# 08_AuxConnectors.net
KiCad netlist of a schematic drawn in Altium Designer
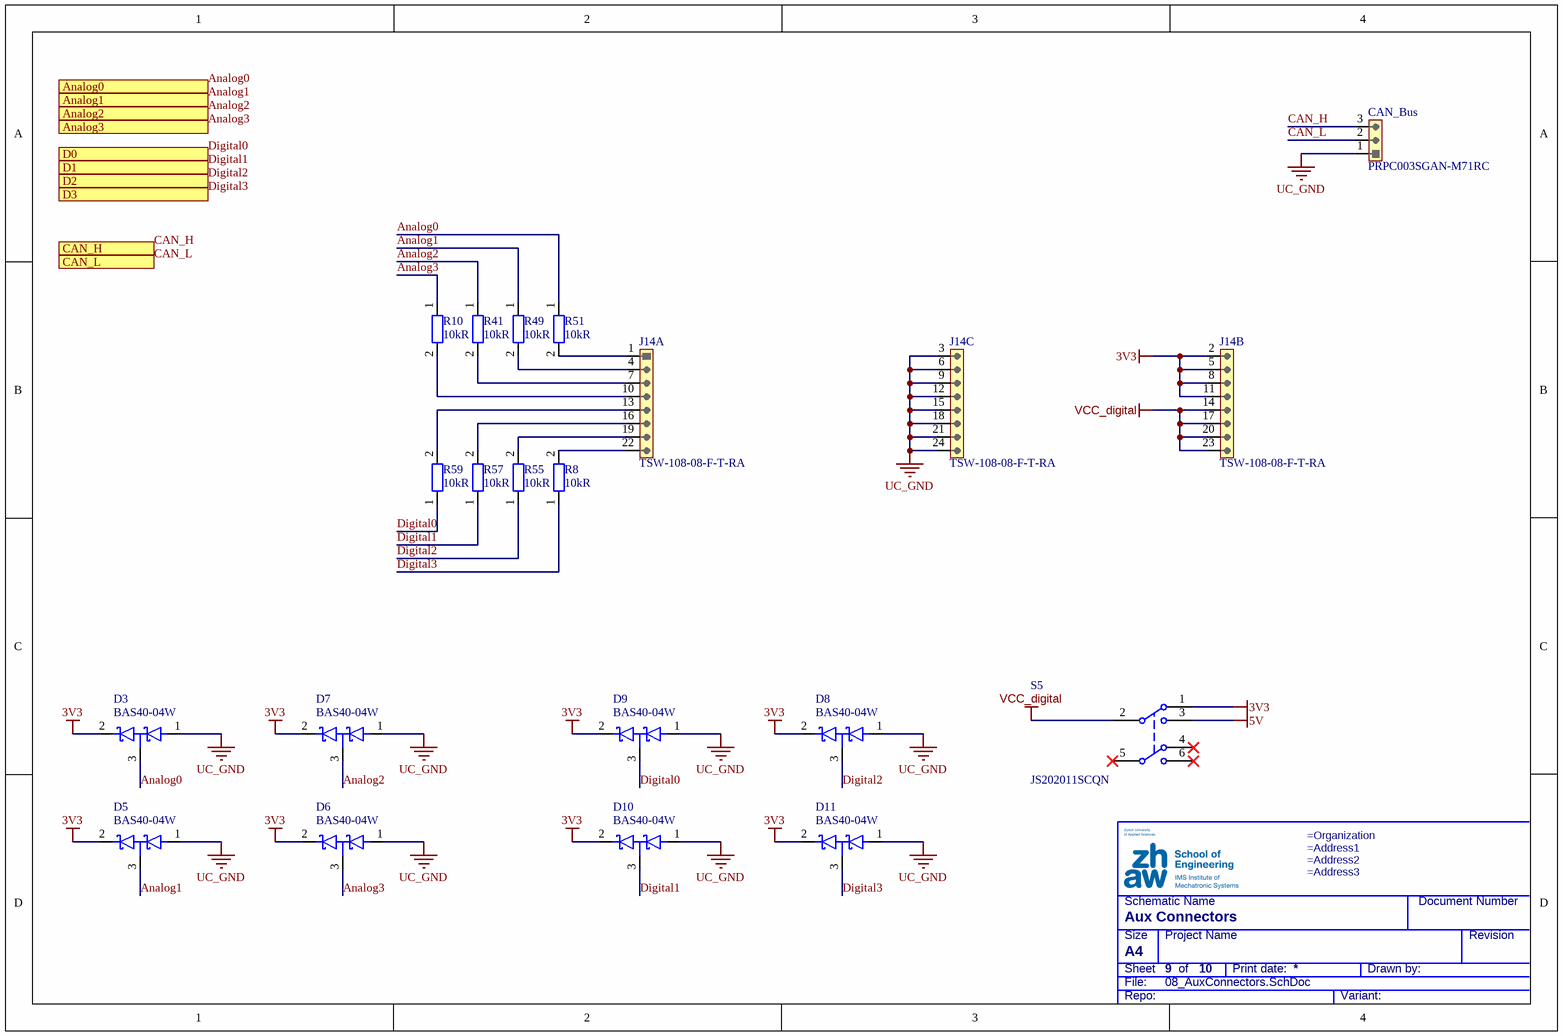
[diagram p0: 08_AuxConnectors.SchDoc]

(export (version "E")
  (design (tool "Eeschema 10.0.6"))
  (components
    (comp (ref "CAN_Bus")
      (value "PRPC003SGAN-M71RC")
      (footprint "HD254_1x3_MH")
      (description "Header, 1x3Pin, Pitch 2.54mm, Male, Horizontal, THT")
      (fields (field (name "MANUFACTURER") "Sullins Connector Solutions"))
      (libsource (lib "Altium Concord Pro on Altium 365") (part "Header 1x03 m"))
    )
    (comp (ref "D3")
      (value "BAS40-04W")
      (footprint "SOT65P220X110-3L")
      (description "Schottky Diode, 40V, 120mA, SOT323, 2 in series")
      (fields (field (name "VOLTAGE") "40V"))
      (libsource (lib "Altium Concord Pro on Altium 365") (part "D-SKY-AKC-3"))
    )
    (comp (ref "D5")
      (value "BAS40-04W")
      (footprint "SOT65P220X110-3L")
      (description "Schottky Diode, 40V, 120mA, SOT323, 2 in series")
      (fields (field (name "VOLTAGE") "40V"))
      (libsource (lib "Altium Concord Pro on Altium 365") (part "D-SKY-AKC-3"))
    )
    (comp (ref "D6")
      (value "BAS40-04W")
      (footprint "SOT65P220X110-3L")
      (description "Schottky Diode, 40V, 120mA, SOT323, 2 in series")
      (fields (field (name "VOLTAGE") "40V"))
      (libsource (lib "Altium Concord Pro on Altium 365") (part "D-SKY-AKC-3"))
    )
    (comp (ref "D7")
      (value "BAS40-04W")
      (footprint "SOT65P220X110-3L")
      (description "Schottky Diode, 40V, 120mA, SOT323, 2 in series")
      (fields (field (name "VOLTAGE") "40V"))
      (libsource (lib "Altium Concord Pro on Altium 365") (part "D-SKY-AKC-3"))
    )
    (comp (ref "D8")
      (value "BAS40-04W")
      (footprint "SOT65P220X110-3L")
      (description "Schottky Diode, 40V, 120mA, SOT323, 2 in series")
      (fields (field (name "VOLTAGE") "40V"))
      (libsource (lib "Altium Concord Pro on Altium 365") (part "D-SKY-AKC-3"))
    )
    (comp (ref "D9")
      (value "BAS40-04W")
      (footprint "SOT65P220X110-3L")
      (description "Schottky Diode, 40V, 120mA, SOT323, 2 in series")
      (fields (field (name "VOLTAGE") "40V"))
      (libsource (lib "Altium Concord Pro on Altium 365") (part "D-SKY-AKC-3"))
    )
    (comp (ref "D10")
      (value "BAS40-04W")
      (footprint "SOT65P220X110-3L")
      (description "Schottky Diode, 40V, 120mA, SOT323, 2 in series")
      (fields (field (name "VOLTAGE") "40V"))
      (libsource (lib "Altium Concord Pro on Altium 365") (part "D-SKY-AKC-3"))
    )
    (comp (ref "D11")
      (value "BAS40-04W")
      (footprint "SOT65P220X110-3L")
      (description "Schottky Diode, 40V, 120mA, SOT323, 2 in series")
      (fields (field (name "VOLTAGE") "40V"))
      (libsource (lib "Altium Concord Pro on Altium 365") (part "D-SKY-AKC-3"))
    )
    (comp (ref "J14")
      (value "TSW-108-08-F-T-RA")
      (footprint "HD254_8x3_MH")
      (description "Header, 3x8Pin, Pitch 2.54mm, Male, Horizontal, THT")
      (fields (field (name "MANUFACTURER") "Samtec"))
      (libsource (lib "Altium Concord Pro on Altium 365") (part "Header 3x08 m"))
    )
    (comp (ref "R8")
      (value "10kR")
      (footprint "RESC1005X04L")
      (description "Res, 10kR, 1%, 0.1W, 0402")
      (fields (field (name "POWER") "100mW") (field (name "TOLERANCE") "1%"))
      (libsource (lib "") (part "RES-2_1"))
    )
    (comp (ref "R10")
      (value "10kR")
      (footprint "RESC1005X04L")
      (description "Res, 10kR, 1%, 0.1W, 0402")
      (fields (field (name "POWER") "100mW") (field (name "TOLERANCE") "1%"))
      (libsource (lib "Altium Concord Pro on Altium 365") (part "RES-2"))
    )
    (comp (ref "R41")
      (value "10kR")
      (footprint "RESC1005X04L")
      (description "Res, 10kR, 1%, 0.1W, 0402")
      (fields (field (name "POWER") "100mW") (field (name "TOLERANCE") "1%"))
      (libsource (lib "Altium Concord Pro on Altium 365") (part "RES-2"))
    )
    (comp (ref "R49")
      (value "10kR")
      (footprint "RESC1005X04L")
      (description "Res, 10kR, 1%, 0.1W, 0402")
      (fields (field (name "POWER") "100mW") (field (name "TOLERANCE") "1%"))
      (libsource (lib "Altium Concord Pro on Altium 365") (part "RES-2"))
    )
    (comp (ref "R51")
      (value "10kR")
      (footprint "RESC1005X04L")
      (description "Res, 10kR, 1%, 0.1W, 0402")
      (fields (field (name "POWER") "100mW") (field (name "TOLERANCE") "1%"))
      (libsource (lib "Altium Concord Pro on Altium 365") (part "RES-2"))
    )
    (comp (ref "R55")
      (value "10kR")
      (footprint "RESC1005X04L")
      (description "Res, 10kR, 1%, 0.1W, 0402")
      (fields (field (name "POWER") "100mW") (field (name "TOLERANCE") "1%"))
      (libsource (lib "") (part "RES-2_1"))
    )
    (comp (ref "R57")
      (value "10kR")
      (footprint "RESC1005X04L")
      (description "Res, 10kR, 1%, 0.1W, 0402")
      (fields (field (name "POWER") "100mW") (field (name "TOLERANCE") "1%"))
      (libsource (lib "") (part "RES-2_1"))
    )
    (comp (ref "R59")
      (value "10kR")
      (footprint "RESC1005X04L")
      (description "Res, 10kR, 1%, 0.1W, 0402")
      (fields (field (name "POWER") "100mW") (field (name "TOLERANCE") "1%"))
      (libsource (lib "") (part "RES-2_1"))
    )
    (comp (ref "S5")
      (value "JS202011SCQN")
      (footprint "SW_JS202011SCQN")
      (description "Slide Switch, Vertical, DPDT, 30V, 100mA, L9B3H3.5")
      (libsource (lib "Altium Concord Pro on Altium 365") (part "SW-DPDT_6"))
    )
  )
  (nets
    (net (code "1") (name "/Analog0") (class "Default")
      (node (ref "D3") (pin "3") (pinfunction "C_3") (pintype "passive"))
      (node (ref "R51") (pin "1") (pinfunction "1_1") (pintype "passive"))
    )
    (net (code "2") (name "/Analog1") (class "Default")
      (node (ref "D5") (pin "3") (pinfunction "C_3") (pintype "passive"))
      (node (ref "R49") (pin "1") (pinfunction "1_1") (pintype "passive"))
    )
    (net (code "3") (name "/Analog2") (class "Default")
      (node (ref "D7") (pin "3") (pinfunction "C_3") (pintype "passive"))
      (node (ref "R41") (pin "1") (pinfunction "1_1") (pintype "passive"))
    )
    (net (code "4") (name "/Analog3") (class "Default")
      (node (ref "D6") (pin "3") (pinfunction "C_3") (pintype "passive"))
      (node (ref "R10") (pin "1") (pinfunction "1_1") (pintype "passive"))
    )
    (net (code "5") (name "/CAN_H") (class "Default")
      (node (ref "CAN_Bus") (pin "3") (pinfunction "3_3") (pintype "passive"))
    )
    (net (code "6") (name "/CAN_L") (class "Default")
      (node (ref "CAN_Bus") (pin "2") (pinfunction "2_2") (pintype "passive"))
    )
    (net (code "7") (name "/Digital0") (class "Default")
      (node (ref "D9") (pin "3") (pinfunction "C_3") (pintype "passive"))
      (node (ref "R59") (pin "1") (pinfunction "1_1") (pintype "passive"))
    )
    (net (code "8") (name "/Digital1") (class "Default")
      (node (ref "D10") (pin "3") (pinfunction "C_3") (pintype "passive"))
      (node (ref "R57") (pin "1") (pinfunction "1_1") (pintype "passive"))
    )
    (net (code "9") (name "/Digital2") (class "Default")
      (node (ref "D8") (pin "3") (pinfunction "C_3") (pintype "passive"))
      (node (ref "R55") (pin "1") (pinfunction "1_1") (pintype "passive"))
    )
    (net (code "10") (name "/Digital3") (class "Default")
      (node (ref "D11") (pin "3") (pinfunction "C_3") (pintype "passive"))
      (node (ref "R8") (pin "1") (pinfunction "1_1") (pintype "passive"))
    )
    (net (code "11") (name "3V3") (class "Default")
      (node (ref "D10") (pin "2") (pinfunction "K_2") (pintype "passive"))
      (node (ref "D11") (pin "2") (pinfunction "K_2") (pintype "passive"))
      (node (ref "D3") (pin "2") (pinfunction "K_2") (pintype "passive"))
      (node (ref "D5") (pin "2") (pinfunction "K_2") (pintype "passive"))
      (node (ref "D6") (pin "2") (pinfunction "K_2") (pintype "passive"))
      (node (ref "D7") (pin "2") (pinfunction "K_2") (pintype "passive"))
      (node (ref "D8") (pin "2") (pinfunction "K_2") (pintype "passive"))
      (node (ref "D9") (pin "2") (pinfunction "K_2") (pintype "passive"))
      (node (ref "J14") (pin "11") (pinfunction "11_11") (pintype "passive"))
      (node (ref "J14") (pin "2") (pinfunction "2_2") (pintype "passive"))
      (node (ref "J14") (pin "5") (pinfunction "5_5") (pintype "passive"))
      (node (ref "J14") (pin "8") (pinfunction "8_8") (pintype "passive"))
      (node (ref "S5") (pin "1") (pinfunction "1_1") (pintype "passive"))
    )
    (net (code "12") (name "5V") (class "Default")
      (node (ref "S5") (pin "3") (pinfunction "3_3") (pintype "passive"))
    )
    (net (code "13") (name "Net-(J14-Pad1)") (class "Default")
      (node (ref "J14") (pin "1") (pinfunction "1_1") (pintype "passive"))
      (node (ref "R51") (pin "2") (pinfunction "2_2") (pintype "passive"))
    )
    (net (code "14") (name "Net-(J14-Pad4)") (class "Default")
      (node (ref "J14") (pin "4") (pinfunction "4_4") (pintype "passive"))
      (node (ref "R49") (pin "2") (pinfunction "2_2") (pintype "passive"))
    )
    (net (code "15") (name "Net-(J14-Pad7)") (class "Default")
      (node (ref "J14") (pin "7") (pinfunction "7_7") (pintype "passive"))
      (node (ref "R41") (pin "2") (pinfunction "2_2") (pintype "passive"))
    )
    (net (code "16") (name "Net-(J14-Pad10)") (class "Default")
      (node (ref "J14") (pin "10") (pinfunction "10_10") (pintype "passive"))
      (node (ref "R10") (pin "2") (pinfunction "2_2") (pintype "passive"))
    )
    (net (code "17") (name "Net-(J14-Pad13)") (class "Default")
      (node (ref "J14") (pin "13") (pinfunction "13_13") (pintype "passive"))
      (node (ref "R59") (pin "2") (pinfunction "2_2") (pintype "passive"))
    )
    (net (code "18") (name "Net-(J14-Pad16)") (class "Default")
      (node (ref "J14") (pin "16") (pinfunction "16_16") (pintype "passive"))
      (node (ref "R57") (pin "2") (pinfunction "2_2") (pintype "passive"))
    )
    (net (code "19") (name "Net-(J14-Pad19)") (class "Default")
      (node (ref "J14") (pin "19") (pinfunction "19_19") (pintype "passive"))
      (node (ref "R55") (pin "2") (pinfunction "2_2") (pintype "passive"))
    )
    (net (code "20") (name "Net-(J14-Pad22)") (class "Default")
      (node (ref "J14") (pin "22") (pinfunction "22_22") (pintype "passive"))
      (node (ref "R8") (pin "2") (pinfunction "2_2") (pintype "passive"))
    )
    (net (code "21") (name "UC_GND") (class "Default")
      (node (ref "CAN_Bus") (pin "1") (pinfunction "1_1") (pintype "passive"))
      (node (ref "D10") (pin "1") (pinfunction "A_1") (pintype "passive"))
      (node (ref "D11") (pin "1") (pinfunction "A_1") (pintype "passive"))
      (node (ref "D3") (pin "1") (pinfunction "A_1") (pintype "passive"))
      (node (ref "D5") (pin "1") (pinfunction "A_1") (pintype "passive"))
      (node (ref "D6") (pin "1") (pinfunction "A_1") (pintype "passive"))
      (node (ref "D7") (pin "1") (pinfunction "A_1") (pintype "passive"))
      (node (ref "D8") (pin "1") (pinfunction "A_1") (pintype "passive"))
      (node (ref "D9") (pin "1") (pinfunction "A_1") (pintype "passive"))
      (node (ref "J14") (pin "12") (pinfunction "12_12") (pintype "passive"))
      (node (ref "J14") (pin "15") (pinfunction "15_15") (pintype "passive"))
      (node (ref "J14") (pin "18") (pinfunction "18_18") (pintype "passive"))
      (node (ref "J14") (pin "21") (pinfunction "21_21") (pintype "passive"))
      (node (ref "J14") (pin "24") (pinfunction "24_24") (pintype "passive"))
      (node (ref "J14") (pin "3") (pinfunction "3_3") (pintype "passive"))
      (node (ref "J14") (pin "6") (pinfunction "6_6") (pintype "passive"))
      (node (ref "J14") (pin "9") (pinfunction "9_9") (pintype "passive"))
    )
    (net (code "22") (name "VCC_digital") (class "Default")
      (node (ref "J14") (pin "14") (pinfunction "14_14") (pintype "passive"))
      (node (ref "J14") (pin "17") (pinfunction "17_17") (pintype "passive"))
      (node (ref "J14") (pin "20") (pinfunction "20_20") (pintype "passive"))
      (node (ref "J14") (pin "23") (pinfunction "23_23") (pintype "passive"))
      (node (ref "S5") (pin "2") (pinfunction "2_2") (pintype "passive"))
    )
    (net (code "23") (name "unconnected-(S5-Pad4)") (class "Default")
      (node (ref "S5") (pin "4") (pinfunction "4_4") (pintype "passive+no_connect"))
    )
    (net (code "24") (name "unconnected-(S5-Pad5)") (class "Default")
      (node (ref "S5") (pin "5") (pinfunction "5_5") (pintype "passive+no_connect"))
    )
    (net (code "25") (name "unconnected-(S5-Pad6)") (class "Default")
      (node (ref "S5") (pin "6") (pinfunction "6_6") (pintype "passive+no_connect"))
    )
  )
)
